# Glasses.net
KiCad netlist of a schematic drawn in Altium Designer
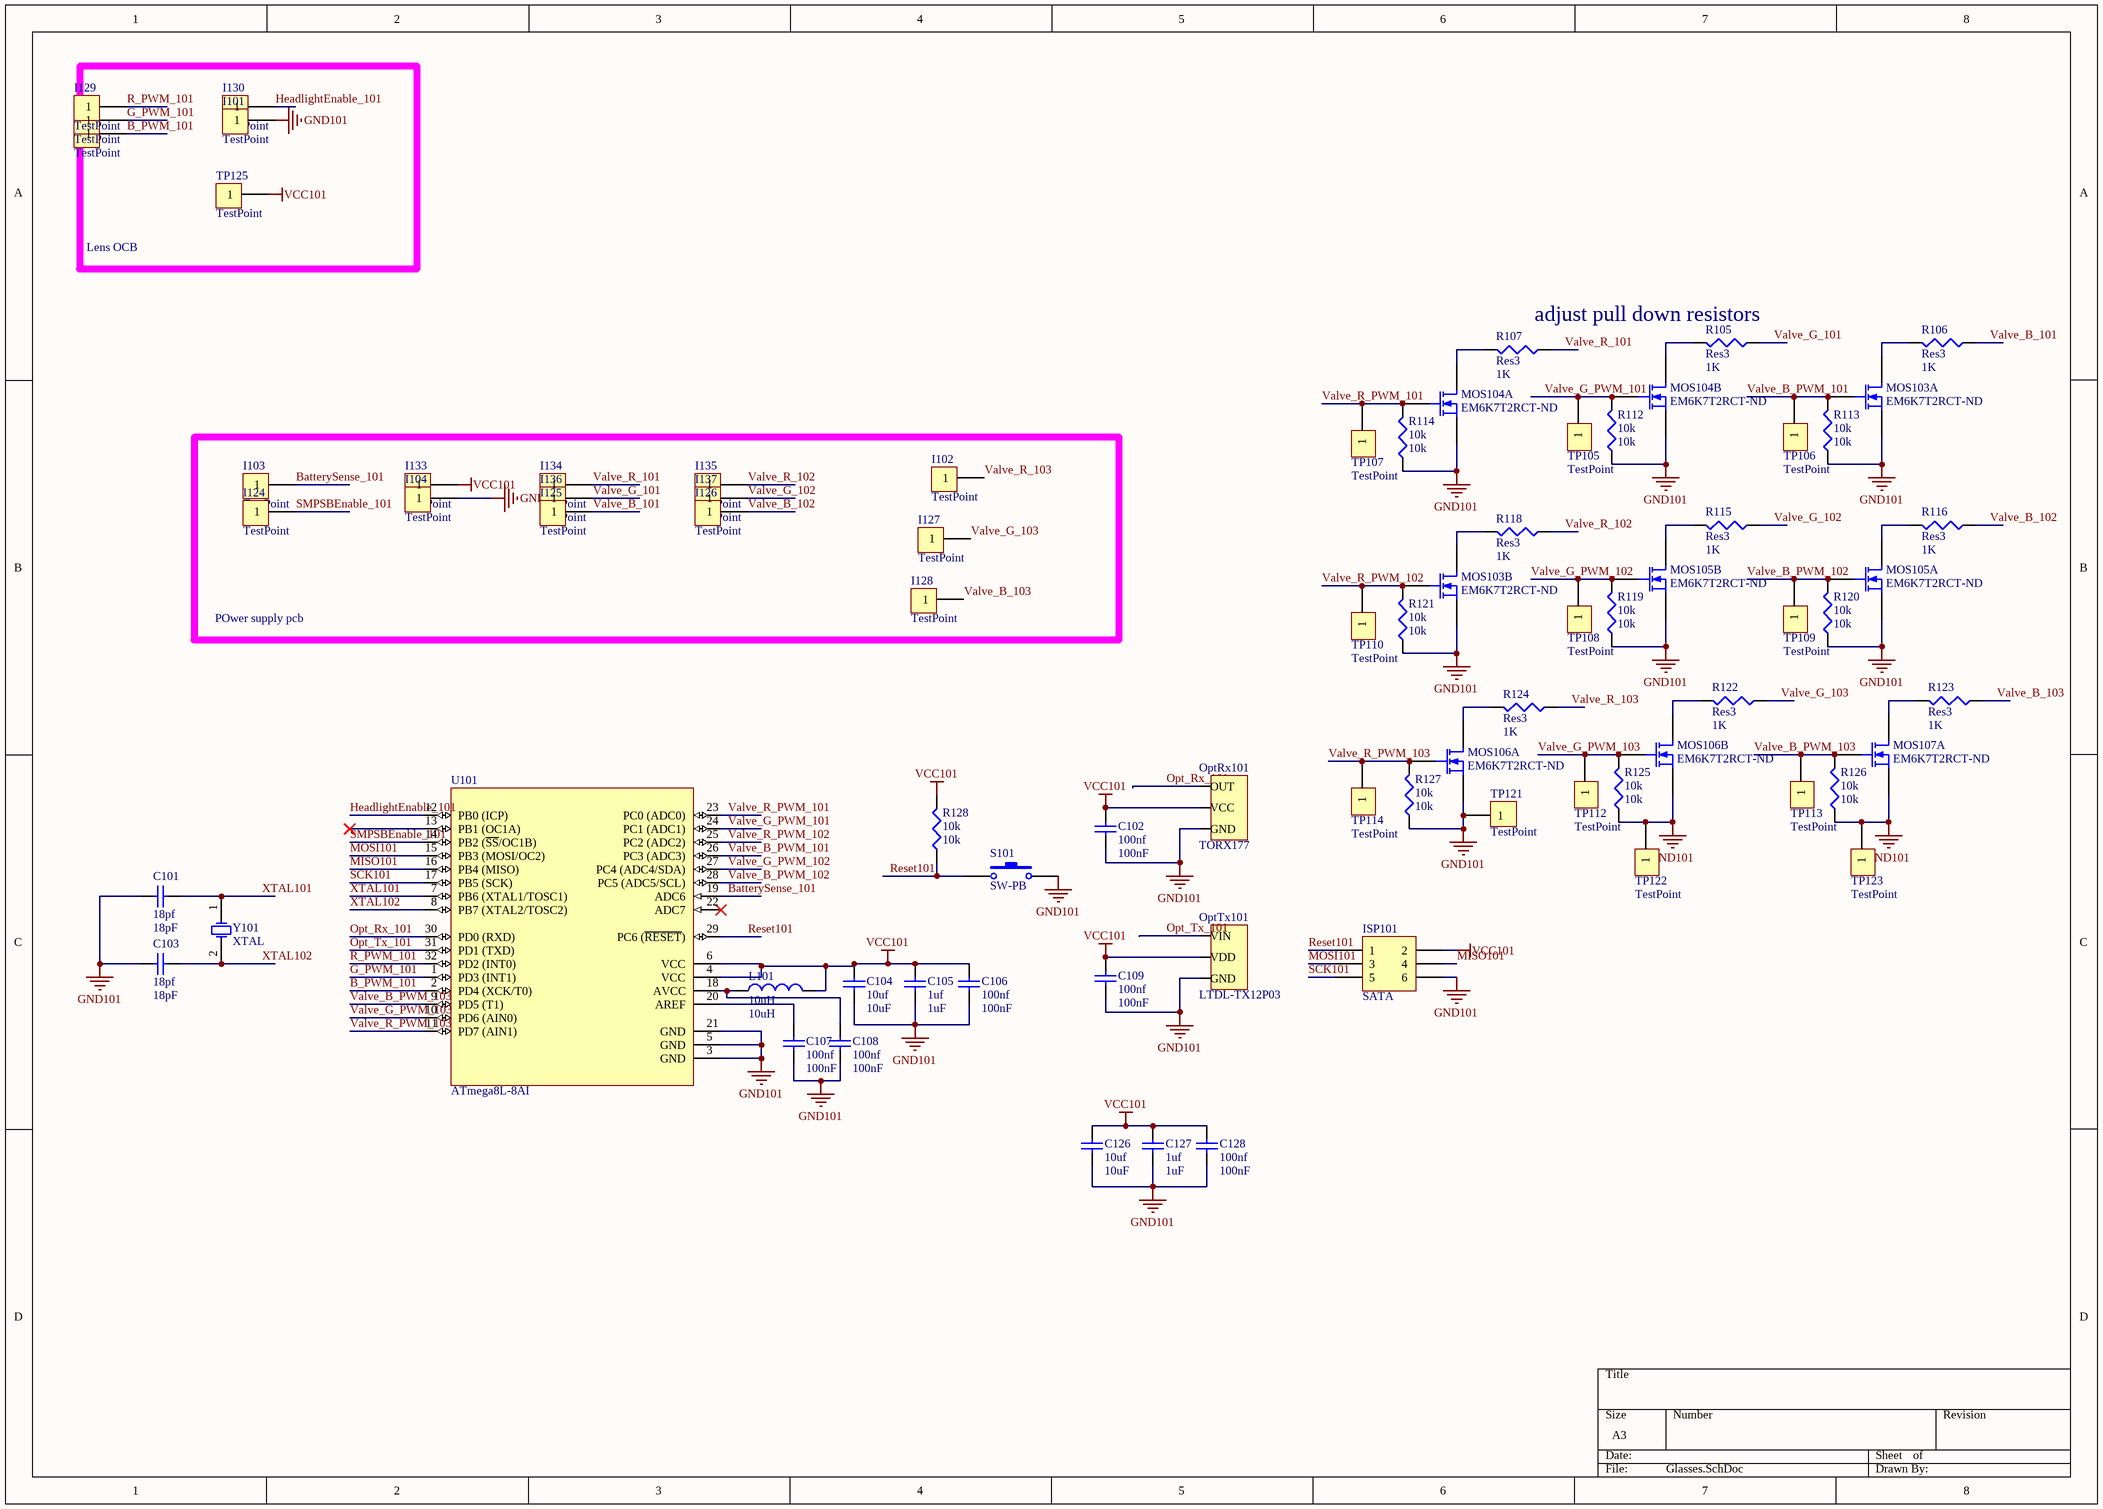
[diagram p0: Glasses.SchDoc]

(export (version "E")
  (design (tool "Eeschema 10.0.6"))
  (components
    (comp (ref "C101")
      (value "18pf")
      (footprint "0603")
      (description "Capacitor (Semiconductor SIM Model)")
      (fields (field (name "ALTIUM_VALUE") "18pF") (field (name "PUBLISHER") "Altium Limited"))
      (libsource (lib "Miscellaneous Devices") (part "Cap Semi"))
    )
    (comp (ref "C102")
      (value "100nf")
      (footprint "0603")
      (description "Capacitor (Semiconductor SIM Model)")
      (fields (field (name "ALTIUM_VALUE") "100nF") (field (name "PUBLISHER") "Altium Limited"))
      (libsource (lib "Miscellaneous Devices") (part "Cap Semi"))
    )
    (comp (ref "C103")
      (value "18pf")
      (footprint "0603")
      (description "Capacitor (Semiconductor SIM Model)")
      (fields (field (name "ALTIUM_VALUE") "18pF") (field (name "PUBLISHER") "Altium Limited"))
      (libsource (lib "Miscellaneous Devices") (part "Cap Semi"))
    )
    (comp (ref "C104")
      (value "10uf")
      (footprint "0805")
      (description "Capacitor (Semiconductor SIM Model)")
      (fields (field (name "ALTIUM_VALUE") "10uF") (field (name "PUBLISHER") "Altium Limited"))
      (libsource (lib "Miscellaneous Devices") (part "Cap Semi"))
    )
    (comp (ref "C105")
      (value "1uf")
      (footprint "0603")
      (description "Capacitor (Semiconductor SIM Model)")
      (fields (field (name "ALTIUM_VALUE") "1uF") (field (name "PUBLISHER") "Altium Limited"))
      (libsource (lib "Miscellaneous Devices") (part "Cap Semi"))
    )
    (comp (ref "C106")
      (value "100nf")
      (footprint "0603")
      (description "Capacitor (Semiconductor SIM Model)")
      (fields (field (name "ALTIUM_VALUE") "100nF") (field (name "PUBLISHER") "Altium Limited"))
      (libsource (lib "Miscellaneous Devices") (part "Cap Semi"))
    )
    (comp (ref "C107")
      (value "100nf")
      (footprint "0603")
      (description "Capacitor (Semiconductor SIM Model)")
      (fields (field (name "ALTIUM_VALUE") "100nF") (field (name "PUBLISHER") "Altium Limited"))
      (libsource (lib "Miscellaneous Devices") (part "Cap Semi"))
    )
    (comp (ref "C108")
      (value "100nf")
      (footprint "0603")
      (description "Capacitor (Semiconductor SIM Model)")
      (fields (field (name "ALTIUM_VALUE") "100nF") (field (name "PUBLISHER") "Altium Limited"))
      (libsource (lib "Miscellaneous Devices") (part "Cap Semi"))
    )
    (comp (ref "C109")
      (value "100nf")
      (footprint "0603")
      (description "Capacitor (Semiconductor SIM Model)")
      (fields (field (name "ALTIUM_VALUE") "100nF") (field (name "PUBLISHER") "Altium Limited"))
      (libsource (lib "Miscellaneous Devices") (part "Cap Semi"))
    )
    (comp (ref "C126")
      (value "10uf")
      (footprint "0805")
      (description "Capacitor (Semiconductor SIM Model)")
      (fields (field (name "ALTIUM_VALUE") "10uF") (field (name "PUBLISHER") "Altium Limited"))
      (libsource (lib "Miscellaneous Devices") (part "Cap Semi"))
    )
    (comp (ref "C127")
      (value "1uf")
      (footprint "0603")
      (description "Capacitor (Semiconductor SIM Model)")
      (fields (field (name "ALTIUM_VALUE") "1uF") (field (name "PUBLISHER") "Altium Limited"))
      (libsource (lib "Miscellaneous Devices") (part "Cap Semi"))
    )
    (comp (ref "C128")
      (value "100nf")
      (footprint "0603")
      (description "Capacitor (Semiconductor SIM Model)")
      (fields (field (name "ALTIUM_VALUE") "100nF") (field (name "PUBLISHER") "Altium Limited"))
      (libsource (lib "Miscellaneous Devices") (part "Cap Semi"))
    )
    (comp (ref "I101")
      (value "TestPoint")
      (footprint "TestPoint")
      (libsource (lib "Schlib1") (part "TestPoint"))
    )
    (comp (ref "I102")
      (value "TestPoint")
      (footprint "TestPoint")
      (libsource (lib "Schlib1") (part "TestPoint"))
    )
    (comp (ref "I103")
      (value "TestPoint")
      (footprint "TestPoint")
      (libsource (lib "Schlib1") (part "TestPoint"))
    )
    (comp (ref "I104")
      (value "TestPoint")
      (footprint "TestPoint")
      (libsource (lib "Schlib1") (part "TestPoint"))
    )
    (comp (ref "I124")
      (value "TestPoint")
      (footprint "TestPoint")
      (libsource (lib "Schlib1") (part "TestPoint"))
    )
    (comp (ref "I125")
      (value "TestPoint")
      (footprint "TestPoint")
      (libsource (lib "Schlib1") (part "TestPoint"))
    )
    (comp (ref "I126")
      (value "TestPoint")
      (footprint "TestPoint")
      (libsource (lib "Schlib1") (part "TestPoint"))
    )
    (comp (ref "I127")
      (value "TestPoint")
      (footprint "TestPoint")
      (libsource (lib "Schlib1") (part "TestPoint"))
    )
    (comp (ref "I128")
      (value "TestPoint")
      (footprint "TestPoint")
      (libsource (lib "Schlib1") (part "TestPoint"))
    )
    (comp (ref "I129")
      (value "TestPoint")
      (footprint "TestPoint")
      (libsource (lib "Schlib1") (part "TestPoint"))
    )
    (comp (ref "I130")
      (value "TestPoint")
      (footprint "TestPoint")
      (libsource (lib "Schlib1") (part "TestPoint"))
    )
    (comp (ref "I131")
      (value "TestPoint")
      (footprint "TestPoint")
      (libsource (lib "Schlib1") (part "TestPoint"))
    )
    (comp (ref "I132")
      (value "TestPoint")
      (footprint "TestPoint")
      (libsource (lib "Schlib1") (part "TestPoint"))
    )
    (comp (ref "I133")
      (value "TestPoint")
      (footprint "TestPoint")
      (libsource (lib "Schlib1") (part "TestPoint"))
    )
    (comp (ref "I134")
      (value "TestPoint")
      (footprint "TestPoint")
      (libsource (lib "Schlib1") (part "TestPoint"))
    )
    (comp (ref "I135")
      (value "TestPoint")
      (footprint "TestPoint")
      (libsource (lib "Schlib1") (part "TestPoint"))
    )
    (comp (ref "I136")
      (value "TestPoint")
      (footprint "TestPoint")
      (libsource (lib "Schlib1") (part "TestPoint"))
    )
    (comp (ref "I137")
      (value "TestPoint")
      (footprint "TestPoint")
      (libsource (lib "Schlib1") (part "TestPoint"))
    )
    (comp (ref "ISP101")
      (value "SATA")
      (footprint "SATA")
      (description "Header, 3-Pin, Dual row")
      (fields (field (name "PUBLISHER") "Altium Limited"))
      (libsource (lib "Miscellaneous Connectors") (part "Header 3X2"))
    )
    (comp (ref "L101")
      (value "10uH")
      (footprint "0805")
      (description "Inductor")
      (fields (field (name "ALTIUM_VALUE") "10uH") (field (name "PUBLISHER") "Altium Limited"))
      (libsource (lib "Miscellaneous Devices") (part "Inductor"))
    )
    (comp (ref "MOS103")
      (value "EM6K7T2RCT-ND")
      (footprint "EM6K7T2R-EMT6")
      (libsource (lib "Schlib1") (part "EM6K7T2RCT-ND"))
    )
    (comp (ref "MOS104")
      (value "EM6K7T2RCT-ND")
      (footprint "EM6K7T2R-EMT6")
      (libsource (lib "Schlib1") (part "EM6K7T2RCT-ND"))
    )
    (comp (ref "MOS105")
      (value "EM6K7T2RCT-ND")
      (footprint "EM6K7T2R-EMT6")
      (libsource (lib "Schlib1") (part "EM6K7T2RCT-ND"))
    )
    (comp (ref "MOS106")
      (value "EM6K7T2RCT-ND")
      (footprint "EM6K7T2R-EMT6")
      (libsource (lib "Schlib1") (part "EM6K7T2RCT-ND"))
    )
    (comp (ref "MOS107")
      (value "EM6K7T2RCT-ND")
      (footprint "EM6K7T2R-EMT6")
      (libsource (lib "Schlib1") (part "EM6K7T2RCT-ND"))
    )
    (comp (ref "OptRx101")
      (value "TORX177")
      (footprint "Optical RX")
      (description "Optical receiver module")
      (libsource (lib "Schlib1") (part "TORX177"))
    )
    (comp (ref "OptTx101")
      (value "LTDL-TX12P03")
      (footprint "Optical TX")
      (description "Optical transmitter")
      (libsource (lib "Schlib1") (part "LTDL-TX12P03"))
    )
    (comp (ref "R105")
      (value "Res3")
      (footprint "0805")
      (description "Resistor")
      (fields (field (name "ALTIUM_VALUE") "1K") (field (name "PUBLISHER") "Altium Limited"))
      (libsource (lib "Miscellaneous Devices") (part "Res3"))
    )
    (comp (ref "R106")
      (value "Res3")
      (footprint "0805")
      (description "Resistor")
      (fields (field (name "ALTIUM_VALUE") "1K") (field (name "PUBLISHER") "Altium Limited"))
      (libsource (lib "Miscellaneous Devices") (part "Res3"))
    )
    (comp (ref "R107")
      (value "Res3")
      (footprint "0805")
      (description "Resistor")
      (fields (field (name "ALTIUM_VALUE") "1K") (field (name "PUBLISHER") "Altium Limited"))
      (libsource (lib "Miscellaneous Devices") (part "Res3"))
    )
    (comp (ref "R112")
      (value "10k")
      (footprint "0603")
      (description "Resistor")
      (fields (field (name "ALTIUM_VALUE") "10k") (field (name "PUBLISHER") "Altium Limited"))
      (libsource (lib "Miscellaneous Devices") (part "Res3"))
    )
    (comp (ref "R113")
      (value "10k")
      (footprint "0603")
      (description "Resistor")
      (fields (field (name "ALTIUM_VALUE") "10k") (field (name "PUBLISHER") "Altium Limited"))
      (libsource (lib "Miscellaneous Devices") (part "Res3"))
    )
    (comp (ref "R114")
      (value "10k")
      (footprint "0603")
      (description "Resistor")
      (fields (field (name "ALTIUM_VALUE") "10k") (field (name "PUBLISHER") "Altium Limited"))
      (libsource (lib "Miscellaneous Devices") (part "Res3"))
    )
    (comp (ref "R115")
      (value "Res3")
      (footprint "0805")
      (description "Resistor")
      (fields (field (name "ALTIUM_VALUE") "1K") (field (name "PUBLISHER") "Altium Limited"))
      (libsource (lib "Miscellaneous Devices") (part "Res3"))
    )
    (comp (ref "R116")
      (value "Res3")
      (footprint "0805")
      (description "Resistor")
      (fields (field (name "ALTIUM_VALUE") "1K") (field (name "PUBLISHER") "Altium Limited"))
      (libsource (lib "Miscellaneous Devices") (part "Res3"))
    )
    (comp (ref "R118")
      (value "Res3")
      (footprint "0805")
      (description "Resistor")
      (fields (field (name "ALTIUM_VALUE") "1K") (field (name "PUBLISHER") "Altium Limited"))
      (libsource (lib "Miscellaneous Devices") (part "Res3"))
    )
    (comp (ref "R119")
      (value "10k")
      (footprint "0603")
      (description "Resistor")
      (fields (field (name "ALTIUM_VALUE") "10k") (field (name "PUBLISHER") "Altium Limited"))
      (libsource (lib "Miscellaneous Devices") (part "Res3"))
    )
    (comp (ref "R120")
      (value "10k")
      (footprint "0603")
      (description "Resistor")
      (fields (field (name "ALTIUM_VALUE") "10k") (field (name "PUBLISHER") "Altium Limited"))
      (libsource (lib "Miscellaneous Devices") (part "Res3"))
    )
    (comp (ref "R121")
      (value "10k")
      (footprint "0603")
      (description "Resistor")
      (fields (field (name "ALTIUM_VALUE") "10k") (field (name "PUBLISHER") "Altium Limited"))
      (libsource (lib "Miscellaneous Devices") (part "Res3"))
    )
    (comp (ref "R122")
      (value "Res3")
      (footprint "0805")
      (description "Resistor")
      (fields (field (name "ALTIUM_VALUE") "1K") (field (name "PUBLISHER") "Altium Limited"))
      (libsource (lib "Miscellaneous Devices") (part "Res3"))
    )
    (comp (ref "R123")
      (value "Res3")
      (footprint "0805")
      (description "Resistor")
      (fields (field (name "ALTIUM_VALUE") "1K") (field (name "PUBLISHER") "Altium Limited"))
      (libsource (lib "Miscellaneous Devices") (part "Res3"))
    )
    (comp (ref "R124")
      (value "Res3")
      (footprint "0805")
      (description "Resistor")
      (fields (field (name "ALTIUM_VALUE") "1K") (field (name "PUBLISHER") "Altium Limited"))
      (libsource (lib "Miscellaneous Devices") (part "Res3"))
    )
    (comp (ref "R125")
      (value "10k")
      (footprint "0603")
      (description "Resistor")
      (fields (field (name "ALTIUM_VALUE") "10k") (field (name "PUBLISHER") "Altium Limited"))
      (libsource (lib "Miscellaneous Devices") (part "Res3"))
    )
    (comp (ref "R126")
      (value "10k")
      (footprint "0603")
      (description "Resistor")
      (fields (field (name "ALTIUM_VALUE") "10k") (field (name "PUBLISHER") "Altium Limited"))
      (libsource (lib "Miscellaneous Devices") (part "Res3"))
    )
    (comp (ref "R127")
      (value "10k")
      (footprint "0603")
      (description "Resistor")
      (fields (field (name "ALTIUM_VALUE") "10k") (field (name "PUBLISHER") "Altium Limited"))
      (libsource (lib "Miscellaneous Devices") (part "Res3"))
    )
    (comp (ref "R128")
      (value "10k")
      (footprint "0603")
      (description "Resistor")
      (fields (field (name "ALTIUM_VALUE") "10k") (field (name "PUBLISHER") "Altium Limited"))
      (libsource (lib "Miscellaneous Devices") (part "Res3"))
    )
    (comp (ref "S101")
      (value "SW-PB")
      (footprint "2 pin switch (surface mount)")
      (description "Switch")
      (fields (field (name "PUBLISHER") "Altium Limited"))
      (libsource (lib "Miscellaneous Devices") (part "SW-PB"))
    )
    (comp (ref "TP105") (value "TestPoint") (footprint "TestPoint") (libsource (lib "") (part "TestPoint_1")))
    (comp (ref "TP106") (value "TestPoint") (footprint "TestPoint") (libsource (lib "") (part "TestPoint_1")))
    (comp (ref "TP107") (value "TestPoint") (footprint "TestPoint") (libsource (lib "") (part "TestPoint_1")))
    (comp (ref "TP108") (value "TestPoint") (footprint "TestPoint") (libsource (lib "") (part "TestPoint_1")))
    (comp (ref "TP109") (value "TestPoint") (footprint "TestPoint") (libsource (lib "") (part "TestPoint_1")))
    (comp (ref "TP110") (value "TestPoint") (footprint "TestPoint") (libsource (lib "") (part "TestPoint_1")))
    (comp (ref "TP112") (value "TestPoint") (footprint "TestPoint") (libsource (lib "") (part "TestPoint_1")))
    (comp (ref "TP113") (value "TestPoint") (footprint "TestPoint") (libsource (lib "") (part "TestPoint_1")))
    (comp (ref "TP114") (value "TestPoint") (footprint "TestPoint") (libsource (lib "") (part "TestPoint_1")))
    (comp (ref "TP121") (value "TestPoint") (footprint "TestPoint") (libsource (lib "") (part "TestPoint_2")))
    (comp (ref "TP122") (value "TestPoint") (footprint "TestPoint") (libsource (lib "") (part "TestPoint_1")))
    (comp (ref "TP123") (value "TestPoint") (footprint "TestPoint") (libsource (lib "") (part "TestPoint_1")))
    (comp (ref "TP125")
      (value "TestPoint")
      (footprint "TestPoint")
      (libsource (lib "Schlib1") (part "TestPoint"))
    )
    (comp (ref "U101")
      (value "ATmega8L-8AI")
      (footprint "ATMega_GOOD")
      (description "8-Bit AVR Microcontroller with 8K Bytes of In-System Programmable Flash Memory")
      (fields (field (name "PUBLISHER") "Altium Limited"))
      (libsource (lib "Atmel Microcontroller 8-Bit AVR") (part "ATmega8L-8AI"))
    )
    (comp (ref "Y101")
      (value "XTAL")
      (footprint "ABLS-16MHz-B4-T")
      (description "Crystal Oscillator")
      (fields (field (name "PUBLISHER") "Altium Limited"))
      (libsource (lib "Miscellaneous Devices") (part "XTAL"))
    )
  )
  (nets
    (net (code "1") (name "/B_PWM_101") (class "Default")
      (node (ref "I132") (pin "1") (pinfunction "1_1") (pintype "passive"))
      (node (ref "U101") (pin "2") (pinfunction "PD4_(XCK/T0)_2") (pintype "bidirectional"))
    )
    (net (code "2") (name "/BatterySense_101") (class "Default")
      (node (ref "I103") (pin "1") (pinfunction "1_1") (pintype "passive"))
      (node (ref "U101") (pin "19") (pinfunction "ADC6_19") (pintype "input"))
    )
    (net (code "3") (name "/G_PWM_101") (class "Default")
      (node (ref "I131") (pin "1") (pinfunction "1_1") (pintype "passive"))
      (node (ref "U101") (pin "1") (pinfunction "PD3_(INT1)_1") (pintype "bidirectional"))
    )
    (net (code "4") (name "/HeadlightEnable_101") (class "Default")
      (node (ref "I130") (pin "1") (pinfunction "1_1") (pintype "passive"))
      (node (ref "U101") (pin "12") (pinfunction "PB0_(ICP)_12") (pintype "bidirectional"))
    )
    (net (code "5") (name "/MISO101") (class "Default")
      (node (ref "ISP101") (pin "4") (pinfunction "4_4") (pintype "passive"))
      (node (ref "U101") (pin "16") (pinfunction "PB4_(MISO)_16") (pintype "bidirectional"))
    )
    (net (code "6") (name "/MOSI101") (class "Default")
      (node (ref "ISP101") (pin "3") (pinfunction "3_3") (pintype "passive"))
      (node (ref "U101") (pin "15") (pinfunction "PB3_(MOSI/OC2)_15") (pintype "bidirectional"))
    )
    (net (code "7") (name "/Opt_Rx_101") (class "Default")
      (node (ref "OptRx101") (pin "1") (pinfunction "OUT_1") (pintype "passive"))
      (node (ref "U101") (pin "30") (pinfunction "PD0_(RXD)_30") (pintype "bidirectional"))
    )
    (net (code "8") (name "/Opt_Tx_101") (class "Default")
      (node (ref "OptTx101") (pin "1") (pinfunction "VIN_1") (pintype "passive"))
      (node (ref "U101") (pin "31") (pinfunction "PD1_(TXD)_31") (pintype "bidirectional"))
    )
    (net (code "9") (name "/R_PWM_101") (class "Default")
      (node (ref "I129") (pin "1") (pinfunction "1_1") (pintype "passive"))
      (node (ref "U101") (pin "32") (pinfunction "PD2_(INT0)_32") (pintype "bidirectional"))
    )
    (net (code "10") (name "/Reset101") (class "Default")
      (node (ref "ISP101") (pin "1") (pinfunction "1_1") (pintype "passive"))
      (node (ref "R128") (pin "1") (pinfunction "1_1") (pintype "passive"))
      (node (ref "S101") (pin "1") (pinfunction "1_1") (pintype "passive"))
      (node (ref "U101") (pin "29") (pinfunction "PC6_(~{RESET})_29") (pintype "bidirectional"))
    )
    (net (code "11") (name "/SCK101") (class "Default")
      (node (ref "ISP101") (pin "5") (pinfunction "5_5") (pintype "passive"))
      (node (ref "U101") (pin "17") (pinfunction "PB5_(SCK)_17") (pintype "bidirectional"))
    )
    (net (code "12") (name "/SMPSBEnable_101") (class "Default")
      (node (ref "I124") (pin "1") (pinfunction "1_1") (pintype "passive"))
      (node (ref "U101") (pin "14") (pinfunction "PB2_(~{SS}/OC1B)_14") (pintype "bidirectional"))
    )
    (net (code "13") (name "/Valve_B_101") (class "Default")
      (node (ref "I125") (pin "1") (pinfunction "1_1") (pintype "passive"))
      (node (ref "R106") (pin "1") (pinfunction "1_1") (pintype "passive"))
    )
    (net (code "14") (name "/Valve_B_102") (class "Default")
      (node (ref "I126") (pin "1") (pinfunction "1_1") (pintype "passive"))
      (node (ref "R116") (pin "1") (pinfunction "1_1") (pintype "passive"))
    )
    (net (code "15") (name "/Valve_B_103") (class "Default")
      (node (ref "I128") (pin "1") (pinfunction "1_1") (pintype "passive"))
      (node (ref "R123") (pin "1") (pinfunction "1_1") (pintype "passive"))
    )
    (net (code "16") (name "/Valve_B_PWM_101") (class "Default")
      (node (ref "MOS103") (pin "2") (pinfunction "G_2") (pintype "passive"))
      (node (ref "R113") (pin "2") (pinfunction "2_2") (pintype "passive"))
      (node (ref "TP106") (pin "1") (pinfunction "1_1") (pintype "passive"))
      (node (ref "U101") (pin "26") (pinfunction "PC3_(ADC3)_26") (pintype "bidirectional"))
    )
    (net (code "17") (name "/Valve_B_PWM_102") (class "Default")
      (node (ref "MOS105") (pin "2") (pinfunction "G_2") (pintype "passive"))
      (node (ref "R120") (pin "2") (pinfunction "2_2") (pintype "passive"))
      (node (ref "TP109") (pin "1") (pinfunction "1_1") (pintype "passive"))
      (node (ref "U101") (pin "28") (pinfunction "PC5_(ADC5/SCL)_28") (pintype "bidirectional"))
    )
    (net (code "18") (name "/Valve_B_PWM_103") (class "Default")
      (node (ref "MOS107") (pin "2") (pinfunction "G_2") (pintype "passive"))
      (node (ref "R126") (pin "2") (pinfunction "2_2") (pintype "passive"))
      (node (ref "TP113") (pin "1") (pinfunction "1_1") (pintype "passive"))
      (node (ref "U101") (pin "9") (pinfunction "PD5_(T1)_9") (pintype "bidirectional"))
    )
    (net (code "19") (name "/Valve_G_101") (class "Default")
      (node (ref "I136") (pin "1") (pinfunction "1_1") (pintype "passive"))
      (node (ref "R105") (pin "1") (pinfunction "1_1") (pintype "passive"))
    )
    (net (code "20") (name "/Valve_G_102") (class "Default")
      (node (ref "I137") (pin "1") (pinfunction "1_1") (pintype "passive"))
      (node (ref "R115") (pin "1") (pinfunction "1_1") (pintype "passive"))
    )
    (net (code "21") (name "/Valve_G_103") (class "Default")
      (node (ref "I127") (pin "1") (pinfunction "1_1") (pintype "passive"))
      (node (ref "R122") (pin "1") (pinfunction "1_1") (pintype "passive"))
    )
    (net (code "22") (name "/Valve_G_PWM_101") (class "Default")
      (node (ref "MOS104") (pin "5") (pinfunction "G_5") (pintype "passive"))
      (node (ref "R112") (pin "2") (pinfunction "2_2") (pintype "passive"))
      (node (ref "TP105") (pin "1") (pinfunction "1_1") (pintype "passive"))
      (node (ref "U101") (pin "24") (pinfunction "PC1_(ADC1)_24") (pintype "bidirectional"))
    )
    (net (code "23") (name "/Valve_G_PWM_102") (class "Default")
      (node (ref "MOS105") (pin "5") (pinfunction "G_5") (pintype "passive"))
      (node (ref "R119") (pin "2") (pinfunction "2_2") (pintype "passive"))
      (node (ref "TP108") (pin "1") (pinfunction "1_1") (pintype "passive"))
      (node (ref "U101") (pin "27") (pinfunction "PC4_(ADC4/SDA)_27") (pintype "bidirectional"))
    )
    (net (code "24") (name "/Valve_G_PWM_103") (class "Default")
      (node (ref "MOS106") (pin "5") (pinfunction "G_5") (pintype "passive"))
      (node (ref "R125") (pin "2") (pinfunction "2_2") (pintype "passive"))
      (node (ref "TP112") (pin "1") (pinfunction "1_1") (pintype "passive"))
      (node (ref "U101") (pin "10") (pinfunction "PD6_(AIN0)_10") (pintype "bidirectional"))
    )
    (net (code "25") (name "/Valve_R_101") (class "Default")
      (node (ref "I134") (pin "1") (pinfunction "1_1") (pintype "passive"))
      (node (ref "R107") (pin "1") (pinfunction "1_1") (pintype "passive"))
    )
    (net (code "26") (name "/Valve_R_102") (class "Default")
      (node (ref "I135") (pin "1") (pinfunction "1_1") (pintype "passive"))
      (node (ref "R118") (pin "1") (pinfunction "1_1") (pintype "passive"))
    )
    (net (code "27") (name "/Valve_R_103") (class "Default")
      (node (ref "I102") (pin "1") (pinfunction "1_1") (pintype "passive"))
      (node (ref "R124") (pin "1") (pinfunction "1_1") (pintype "passive"))
    )
    (net (code "28") (name "/Valve_R_PWM_101") (class "Default")
      (node (ref "MOS104") (pin "2") (pinfunction "G_2") (pintype "passive"))
      (node (ref "R114") (pin "2") (pinfunction "2_2") (pintype "passive"))
      (node (ref "TP107") (pin "1") (pinfunction "1_1") (pintype "passive"))
      (node (ref "U101") (pin "23") (pinfunction "PC0_(ADC0)_23") (pintype "bidirectional"))
    )
    (net (code "29") (name "/Valve_R_PWM_102") (class "Default")
      (node (ref "MOS103") (pin "5") (pinfunction "G_5") (pintype "passive"))
      (node (ref "R121") (pin "2") (pinfunction "2_2") (pintype "passive"))
      (node (ref "TP110") (pin "1") (pinfunction "1_1") (pintype "passive"))
      (node (ref "U101") (pin "25") (pinfunction "PC2_(ADC2)_25") (pintype "bidirectional"))
    )
    (net (code "30") (name "/Valve_R_PWM_103") (class "Default")
      (node (ref "MOS106") (pin "2") (pinfunction "G_2") (pintype "passive"))
      (node (ref "R127") (pin "2") (pinfunction "2_2") (pintype "passive"))
      (node (ref "TP114") (pin "1") (pinfunction "1_1") (pintype "passive"))
      (node (ref "U101") (pin "11") (pinfunction "PD7_(AIN1)_11") (pintype "bidirectional"))
    )
    (net (code "31") (name "/XTAL101") (class "Default")
      (node (ref "C101") (pin "2") (pinfunction "2_2") (pintype "passive"))
      (node (ref "U101") (pin "7") (pinfunction "PB6_(XTAL1/TOSC1)_7") (pintype "bidirectional"))
      (node (ref "Y101") (pin "1") (pinfunction "OSC1_1") (pintype "passive"))
    )
    (net (code "32") (name "/XTAL102") (class "Default")
      (node (ref "C103") (pin "2") (pinfunction "2_2") (pintype "passive"))
      (node (ref "U101") (pin "8") (pinfunction "PB7_(XTAL2/TOSC2)_8") (pintype "bidirectional"))
      (node (ref "Y101") (pin "2") (pinfunction "OSC2_2") (pintype "passive"))
    )
    (net (code "33") (name "GND101") (class "Default")
      (node (ref "C101") (pin "1") (pinfunction "1_1") (pintype "passive"))
      (node (ref "C102") (pin "1") (pinfunction "1_1") (pintype "passive"))
      (node (ref "C103") (pin "1") (pinfunction "1_1") (pintype "passive"))
      (node (ref "C104") (pin "1") (pinfunction "1_1") (pintype "passive"))
      (node (ref "C105") (pin "1") (pinfunction "1_1") (pintype "passive"))
      (node (ref "C106") (pin "1") (pinfunction "1_1") (pintype "passive"))
      (node (ref "C107") (pin "1") (pinfunction "1_1") (pintype "passive"))
      (node (ref "C108") (pin "1") (pinfunction "1_1") (pintype "passive"))
      (node (ref "C109") (pin "1") (pinfunction "1_1") (pintype "passive"))
      (node (ref "C126") (pin "1") (pinfunction "1_1") (pintype "passive"))
      (node (ref "C127") (pin "1") (pinfunction "1_1") (pintype "passive"))
      (node (ref "C128") (pin "1") (pinfunction "1_1") (pintype "passive"))
      (node (ref "I101") (pin "1") (pinfunction "1_1") (pintype "passive"))
      (node (ref "I104") (pin "1") (pinfunction "1_1") (pintype "passive"))
      (node (ref "ISP101") (pin "6") (pinfunction "6_6") (pintype "passive"))
      (node (ref "MOS103") (pin "3") (pinfunction "S_3") (pintype "passive"))
      (node (ref "MOS103") (pin "6") (pinfunction "S_6") (pintype "passive"))
      (node (ref "MOS104") (pin "3") (pinfunction "S_3") (pintype "passive"))
      (node (ref "MOS104") (pin "6") (pinfunction "S_6") (pintype "passive"))
      (node (ref "MOS105") (pin "3") (pinfunction "S_3") (pintype "passive"))
      (node (ref "MOS105") (pin "6") (pinfunction "S_6") (pintype "passive"))
      (node (ref "MOS106") (pin "3") (pinfunction "S_3") (pintype "passive"))
      (node (ref "MOS106") (pin "6") (pinfunction "S_6") (pintype "passive"))
      (node (ref "MOS107") (pin "3") (pinfunction "S_3") (pintype "passive"))
      (node (ref "OptRx101") (pin "3") (pinfunction "GND_3") (pintype "passive"))
      (node (ref "OptTx101") (pin "3") (pinfunction "GND_3") (pintype "passive"))
      (node (ref "R112") (pin "1") (pinfunction "1_1") (pintype "passive"))
      (node (ref "R113") (pin "1") (pinfunction "1_1") (pintype "passive"))
      (node (ref "R114") (pin "1") (pinfunction "1_1") (pintype "passive"))
      (node (ref "R119") (pin "1") (pinfunction "1_1") (pintype "passive"))
      (node (ref "R120") (pin "1") (pinfunction "1_1") (pintype "passive"))
      (node (ref "R121") (pin "1") (pinfunction "1_1") (pintype "passive"))
      (node (ref "R125") (pin "1") (pinfunction "1_1") (pintype "passive"))
      (node (ref "R126") (pin "1") (pinfunction "1_1") (pintype "passive"))
      (node (ref "R127") (pin "1") (pinfunction "1_1") (pintype "passive"))
      (node (ref "S101") (pin "2") (pinfunction "2_2") (pintype "passive"))
      (node (ref "TP121") (pin "1") (pinfunction "1_1") (pintype "passive"))
      (node (ref "TP122") (pin "1") (pinfunction "1_1") (pintype "passive"))
      (node (ref "TP123") (pin "1") (pinfunction "1_1") (pintype "passive"))
      (node (ref "U101") (pin "21") (pinfunction "GND_21") (pintype "power_in"))
      (node (ref "U101") (pin "3") (pinfunction "GND_3") (pintype "power_in"))
      (node (ref "U101") (pin "5") (pinfunction "GND_5") (pintype "power_in"))
    )
    (net (code "34") (name "Net-(MOS103A-D)") (class "Default")
      (node (ref "MOS103") (pin "1") (pinfunction "D_1") (pintype "passive"))
      (node (ref "R106") (pin "2") (pinfunction "2_2") (pintype "passive"))
    )
    (net (code "35") (name "Net-(MOS103B-D)") (class "Default")
      (node (ref "MOS103") (pin "4") (pinfunction "D_4") (pintype "passive"))
      (node (ref "R118") (pin "2") (pinfunction "2_2") (pintype "passive"))
    )
    (net (code "36") (name "Net-(MOS104A-D)") (class "Default")
      (node (ref "MOS104") (pin "1") (pinfunction "D_1") (pintype "passive"))
      (node (ref "R107") (pin "2") (pinfunction "2_2") (pintype "passive"))
    )
    (net (code "37") (name "Net-(MOS104B-D)") (class "Default")
      (node (ref "MOS104") (pin "4") (pinfunction "D_4") (pintype "passive"))
      (node (ref "R105") (pin "2") (pinfunction "2_2") (pintype "passive"))
    )
    (net (code "38") (name "Net-(MOS105A-D)") (class "Default")
      (node (ref "MOS105") (pin "1") (pinfunction "D_1") (pintype "passive"))
      (node (ref "R116") (pin "2") (pinfunction "2_2") (pintype "passive"))
    )
    (net (code "39") (name "Net-(MOS105B-D)") (class "Default")
      (node (ref "MOS105") (pin "4") (pinfunction "D_4") (pintype "passive"))
      (node (ref "R115") (pin "2") (pinfunction "2_2") (pintype "passive"))
    )
    (net (code "40") (name "Net-(MOS106A-D)") (class "Default")
      (node (ref "MOS106") (pin "1") (pinfunction "D_1") (pintype "passive"))
      (node (ref "R124") (pin "2") (pinfunction "2_2") (pintype "passive"))
    )
    (net (code "41") (name "Net-(MOS106B-D)") (class "Default")
      (node (ref "MOS106") (pin "4") (pinfunction "D_4") (pintype "passive"))
      (node (ref "R122") (pin "2") (pinfunction "2_2") (pintype "passive"))
    )
    (net (code "42") (name "Net-(MOS107A-D)") (class "Default")
      (node (ref "MOS107") (pin "1") (pinfunction "D_1") (pintype "passive"))
      (node (ref "R123") (pin "2") (pinfunction "2_2") (pintype "passive"))
    )
    (net (code "43") (name "Net-(U101-AREF)") (class "Default")
      (node (ref "C107") (pin "2") (pinfunction "2_2") (pintype "passive"))
      (node (ref "U101") (pin "20") (pinfunction "AREF_20") (pintype "passive"))
    )
    (net (code "44") (name "Net-(U101-AVCC)") (class "Default")
      (node (ref "C108") (pin "2") (pinfunction "2_2") (pintype "passive"))
      (node (ref "L101") (pin "1") (pinfunction "1_1") (pintype "passive"))
      (node (ref "U101") (pin "18") (pinfunction "AVCC_18") (pintype "power_in"))
    )
    (net (code "45") (name "VCC101") (class "Default")
      (node (ref "C102") (pin "2") (pinfunction "2_2") (pintype "passive"))
      (node (ref "C104") (pin "2") (pinfunction "2_2") (pintype "passive"))
      (node (ref "C105") (pin "2") (pinfunction "2_2") (pintype "passive"))
      (node (ref "C106") (pin "2") (pinfunction "2_2") (pintype "passive"))
      (node (ref "C109") (pin "2") (pinfunction "2_2") (pintype "passive"))
      (node (ref "C126") (pin "2") (pinfunction "2_2") (pintype "passive"))
      (node (ref "C127") (pin "2") (pinfunction "2_2") (pintype "passive"))
      (node (ref "C128") (pin "2") (pinfunction "2_2") (pintype "passive"))
      (node (ref "I133") (pin "1") (pinfunction "1_1") (pintype "passive"))
      (node (ref "ISP101") (pin "2") (pinfunction "2_2") (pintype "passive"))
      (node (ref "L101") (pin "2") (pinfunction "2_2") (pintype "passive"))
      (node (ref "OptRx101") (pin "2") (pinfunction "VCC_2") (pintype "passive"))
      (node (ref "OptTx101") (pin "2") (pinfunction "VDD_2") (pintype "passive"))
      (node (ref "R128") (pin "2") (pinfunction "2_2") (pintype "passive"))
      (node (ref "TP125") (pin "1") (pinfunction "1_1") (pintype "passive"))
      (node (ref "U101") (pin "4") (pinfunction "VCC_4") (pintype "power_in"))
      (node (ref "U101") (pin "6") (pinfunction "VCC_6") (pintype "power_in"))
    )
    (net (code "46") (name "unconnected-(U101-ADC7-Pad22)") (class "Default")
      (node (ref "U101") (pin "22") (pinfunction "ADC7_22") (pintype "input+no_connect"))
    )
    (net (code "47") (name "unconnected-(U101-PB1_(OC1A)-Pad13)") (class "Default")
      (node (ref "U101") (pin "13") (pinfunction "PB1_(OC1A)_13") (pintype "bidirectional+no_connect"))
    )
  )
)
